# mirror_watchwinder.net
KiCad netlist of a schematic drawn in EAGLE
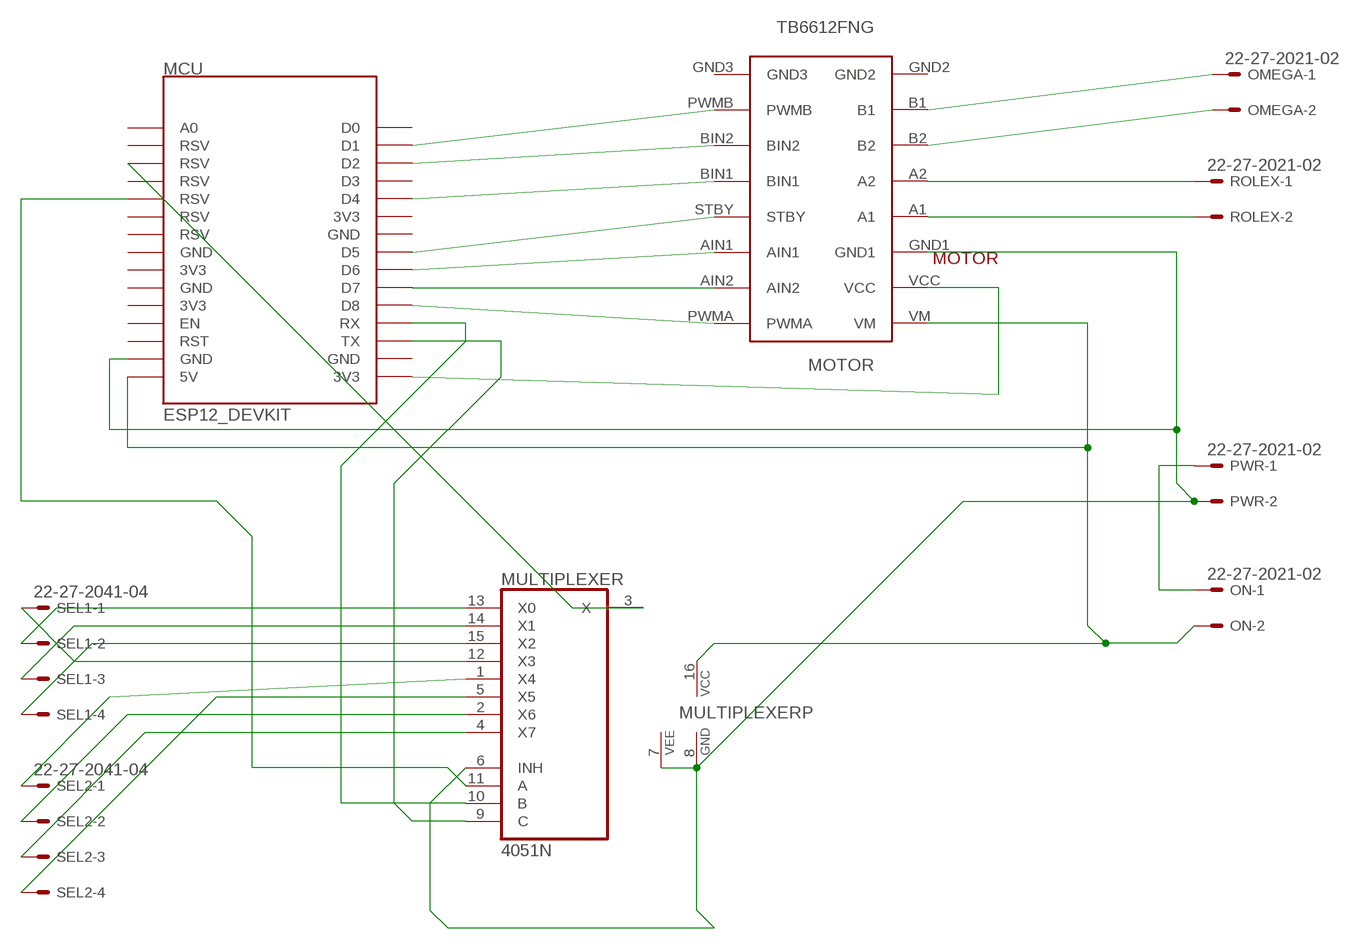
[diagram p0: schematic, sheet 1]

(export (version "E")
  (design (tool "Eeschema 10.0.6"))
  (components
    (comp (ref "MCU")
      (value "ESP12_DEVKIT")
      (footprint "eagle-import:ESP12_DEVKIT")
      (libsource (lib "eagle-import") (part "ESP12_DEVKIT"))
    )
    (comp (ref "MOTOR")
      (value "TB6612FNG")
      (footprint "eagle-import:TB6612FNG")
      (libsource (lib "eagle-import") (part "TB6612FNG"))
    )
    (comp (ref "MULTIPLEXER")
      (value "4051N")
      (footprint "eagle-import:DIL16")
      (libsource (lib "eagle-import") (part "4051N"))
    )
    (comp (ref "OMEGA")
      (value "22-27-2021-02")
      (footprint "eagle-import:6410-02")
      (libsource (lib "eagle-import") (part "22-?-0227-2021"))
    )
    (comp (ref "ON")
      (value "22-27-2021-02")
      (footprint "eagle-import:6410-02")
      (libsource (lib "eagle-import") (part "22-?-0227-2021"))
    )
    (comp (ref "PWR")
      (value "22-27-2021-02")
      (footprint "eagle-import:6410-02")
      (libsource (lib "eagle-import") (part "22-?-0227-2021"))
    )
    (comp (ref "ROLEX")
      (value "22-27-2021-02")
      (footprint "eagle-import:6410-02")
      (libsource (lib "eagle-import") (part "22-?-0227-2021"))
    )
    (comp (ref "SEL1")
      (value "22-27-2041-04")
      (footprint "eagle-import:6410-04")
      (libsource (lib "eagle-import") (part "22-?-0427-2041"))
    )
    (comp (ref "SEL2")
      (value "22-27-2041-04")
      (footprint "eagle-import:6410-04")
      (libsource (lib "eagle-import") (part "22-?-0427-2041"))
    )
  )
  (nets
    (net (code "1") (name "Net-(MCU-3V3-Pad3V3@2)") (class "Default")
      (node (ref "MCU") (pin "3V3@2") (pinfunction "3V3_3V3@2") (pintype "bidirectional"))
      (node (ref "MOTOR") (pin "VCC") (pinfunction "VCC_VCC") (pintype "bidirectional"))
    )
    (net (code "2") (name "Net-(MCU-PadD1)") (class "Default")
      (node (ref "MCU") (pin "D1") (pinfunction "D1_D1") (pintype "bidirectional"))
      (node (ref "MOTOR") (pin "PWMB") (pinfunction "PWMB_PWMB") (pintype "bidirectional"))
    )
    (net (code "3") (name "Net-(MCU-PadD2)") (class "Default")
      (node (ref "MCU") (pin "D2") (pinfunction "D2_D2") (pintype "bidirectional"))
      (node (ref "MOTOR") (pin "BIN2") (pinfunction "BIN2_BIN2") (pintype "bidirectional"))
    )
    (net (code "4") (name "Net-(MCU-PadD4)") (class "Default")
      (node (ref "MCU") (pin "D4") (pinfunction "D4_D4") (pintype "bidirectional"))
      (node (ref "MOTOR") (pin "BIN1") (pinfunction "BIN1_BIN1") (pintype "bidirectional"))
    )
    (net (code "5") (name "Net-(MCU-PadD5)") (class "Default")
      (node (ref "MCU") (pin "D5") (pinfunction "D5_D5") (pintype "bidirectional"))
      (node (ref "MOTOR") (pin "STBY") (pinfunction "STBY_STBY") (pintype "bidirectional"))
    )
    (net (code "6") (name "Net-(MCU-PadD6)") (class "Default")
      (node (ref "MCU") (pin "D6") (pinfunction "D6_D6") (pintype "bidirectional"))
      (node (ref "MOTOR") (pin "AIN1") (pinfunction "AIN1_AIN1") (pintype "bidirectional"))
    )
    (net (code "7") (name "Net-(MCU-PadD7)") (class "Default")
      (node (ref "MCU") (pin "D7") (pinfunction "D7_D7") (pintype "bidirectional"))
      (node (ref "MOTOR") (pin "AIN2") (pinfunction "AIN2_AIN2") (pintype "bidirectional"))
    )
    (net (code "8") (name "Net-(MCU-PadD8)") (class "Default")
      (node (ref "MCU") (pin "D8") (pinfunction "D8_D8") (pintype "bidirectional"))
      (node (ref "MOTOR") (pin "PWMA") (pinfunction "PWMA_PWMA") (pintype "bidirectional"))
    )
    (net (code "9") (name "Net-(MULTIPLEXERA-A)") (class "Default")
      (node (ref "MCU") (pin "RSV@3") (pinfunction "RSV_RSV@3") (pintype "bidirectional"))
      (node (ref "MULTIPLEXER") (pin "11") (pinfunction "A_11") (pintype "input"))
    )
    (net (code "10") (name "Net-(MULTIPLEXERA-B)") (class "Default")
      (node (ref "MCU") (pin "RX") (pinfunction "RX_RX") (pintype "bidirectional"))
      (node (ref "MULTIPLEXER") (pin "10") (pinfunction "B_10") (pintype "input"))
    )
    (net (code "11") (name "Net-(MULTIPLEXERA-C)") (class "Default")
      (node (ref "MCU") (pin "TX") (pinfunction "TX_TX") (pintype "bidirectional"))
      (node (ref "MULTIPLEXER") (pin "9") (pinfunction "C_9") (pintype "input"))
    )
    (net (code "12") (name "Net-(MULTIPLEXERA-INH)") (class "Default")
      (node (ref "MCU") (pin "GND@1") (pinfunction "GND_GND@1") (pintype "bidirectional"))
      (node (ref "MOTOR") (pin "GND1") (pinfunction "GND1_GND1") (pintype "bidirectional"))
      (node (ref "MULTIPLEXER") (pin "6") (pinfunction "INH_6") (pintype "input"))
      (node (ref "MULTIPLEXER") (pin "7") (pinfunction "VEE_7") (pintype "power_in"))
      (node (ref "MULTIPLEXER") (pin "8") (pinfunction "GND_8") (pintype "power_in"))
      (node (ref "PWR") (pin "2") (pinfunction "S_2") (pintype "passive"))
    )
    (net (code "13") (name "Net-(MULTIPLEXERA-X)") (class "Default")
      (node (ref "MCU") (pin "RSV@1") (pinfunction "RSV_RSV@1") (pintype "bidirectional"))
      (node (ref "MULTIPLEXER") (pin "3") (pinfunction "X_3") (pintype "bidirectional"))
    )
    (net (code "14") (name "Net-(MULTIPLEXERA-X0)") (class "Default")
      (node (ref "MULTIPLEXER") (pin "13") (pinfunction "X0_13") (pintype "bidirectional"))
      (node (ref "SEL1") (pin "2") (pinfunction "S_2") (pintype "passive"))
    )
    (net (code "15") (name "Net-(MULTIPLEXERA-X1)") (class "Default")
      (node (ref "MULTIPLEXER") (pin "14") (pinfunction "X1_14") (pintype "bidirectional"))
      (node (ref "SEL1") (pin "3") (pinfunction "S_3") (pintype "passive"))
    )
    (net (code "16") (name "Net-(MULTIPLEXERA-X2)") (class "Default")
      (node (ref "MULTIPLEXER") (pin "15") (pinfunction "X2_15") (pintype "bidirectional"))
      (node (ref "SEL1") (pin "4") (pinfunction "S_4") (pintype "passive"))
    )
    (net (code "17") (name "Net-(MULTIPLEXERA-X3)") (class "Default")
      (node (ref "MULTIPLEXER") (pin "12") (pinfunction "X3_12") (pintype "bidirectional"))
      (node (ref "SEL1") (pin "1") (pinfunction "S_1") (pintype "passive"))
    )
    (net (code "18") (name "Net-(MULTIPLEXERA-X4)") (class "Default")
      (node (ref "MULTIPLEXER") (pin "1") (pinfunction "X4_1") (pintype "bidirectional"))
      (node (ref "SEL2") (pin "1") (pinfunction "S_1") (pintype "passive"))
    )
    (net (code "19") (name "Net-(MULTIPLEXERA-X5)") (class "Default")
      (node (ref "MULTIPLEXER") (pin "5") (pinfunction "X5_5") (pintype "bidirectional"))
      (node (ref "SEL2") (pin "4") (pinfunction "S_4") (pintype "passive"))
    )
    (net (code "20") (name "Net-(MULTIPLEXERA-X6)") (class "Default")
      (node (ref "MULTIPLEXER") (pin "2") (pinfunction "X6_2") (pintype "bidirectional"))
      (node (ref "SEL2") (pin "2") (pinfunction "S_2") (pintype "passive"))
    )
    (net (code "21") (name "Net-(MULTIPLEXERA-X7)") (class "Default")
      (node (ref "MULTIPLEXER") (pin "4") (pinfunction "X7_4") (pintype "bidirectional"))
      (node (ref "SEL2") (pin "3") (pinfunction "S_3") (pintype "passive"))
    )
    (net (code "22") (name "Net-(MULTIPLEXERB-VCC)") (class "Default")
      (node (ref "MCU") (pin "5V") (pinfunction "5V_5V") (pintype "bidirectional"))
      (node (ref "MOTOR") (pin "VM") (pinfunction "VM_VM") (pintype "bidirectional"))
      (node (ref "MULTIPLEXER") (pin "16") (pinfunction "VCC_16") (pintype "power_in"))
      (node (ref "ON") (pin "2") (pinfunction "S_2") (pintype "passive"))
    )
    (net (code "23") (name "Net-(OMEGAA-S)") (class "Default")
      (node (ref "MOTOR") (pin "B1") (pinfunction "B1_B1") (pintype "bidirectional"))
      (node (ref "OMEGA") (pin "1") (pinfunction "S_1") (pintype "passive"))
    )
    (net (code "24") (name "Net-(OMEGAB-S)") (class "Default")
      (node (ref "MOTOR") (pin "B2") (pinfunction "B2_B2") (pintype "bidirectional"))
      (node (ref "OMEGA") (pin "2") (pinfunction "S_2") (pintype "passive"))
    )
    (net (code "25") (name "Net-(ONA-S)") (class "Default")
      (node (ref "ON") (pin "1") (pinfunction "S_1") (pintype "passive"))
      (node (ref "PWR") (pin "1") (pinfunction "S_1") (pintype "passive"))
    )
    (net (code "26") (name "Net-(ROLEXA-S)") (class "Default")
      (node (ref "MOTOR") (pin "A2") (pinfunction "A2_A2") (pintype "bidirectional"))
      (node (ref "ROLEX") (pin "1") (pinfunction "S_1") (pintype "passive"))
    )
    (net (code "27") (name "Net-(ROLEXB-S)") (class "Default")
      (node (ref "MOTOR") (pin "A1") (pinfunction "A1_A1") (pintype "bidirectional"))
      (node (ref "ROLEX") (pin "2") (pinfunction "S_2") (pintype "passive"))
    )
    (net (code "28") (name "unconnected-(MCU-3V3-Pad3V3@0)") (class "Default")
      (node (ref "MCU") (pin "3V3@0") (pinfunction "3V3_3V3@0") (pintype "bidirectional"))
    )
    (net (code "29") (name "unconnected-(MCU-3V3-Pad3V3@1)") (class "Default")
      (node (ref "MCU") (pin "3V3@1") (pinfunction "3V3_3V3@1") (pintype "bidirectional"))
    )
    (net (code "30") (name "unconnected-(MCU-3V3-Pad3V3@3)") (class "Default")
      (node (ref "MCU") (pin "3V3@3") (pinfunction "3V3_3V3@3") (pintype "bidirectional"))
    )
    (net (code "31") (name "unconnected-(MCU-GND-PadGND@0)") (class "Default")
      (node (ref "MCU") (pin "GND@0") (pinfunction "GND_GND@0") (pintype "bidirectional"))
    )
    (net (code "32") (name "unconnected-(MCU-GND-PadGND@2)") (class "Default")
      (node (ref "MCU") (pin "GND@2") (pinfunction "GND_GND@2") (pintype "bidirectional"))
    )
    (net (code "33") (name "unconnected-(MCU-GND-PadGND@3)") (class "Default")
      (node (ref "MCU") (pin "GND@3") (pinfunction "GND_GND@3") (pintype "bidirectional"))
    )
    (net (code "34") (name "unconnected-(MCU-GND-PadGND@4)") (class "Default")
      (node (ref "MCU") (pin "GND@4") (pinfunction "GND_GND@4") (pintype "bidirectional"))
    )
    (net (code "35") (name "unconnected-(MCU-PadA0)") (class "Default")
      (node (ref "MCU") (pin "A0") (pinfunction "A0_A0") (pintype "bidirectional"))
    )
    (net (code "36") (name "unconnected-(MCU-PadD0)") (class "Default")
      (node (ref "MCU") (pin "D0") (pinfunction "D0_D0") (pintype "bidirectional"))
    )
    (net (code "37") (name "unconnected-(MCU-PadD3)") (class "Default")
      (node (ref "MCU") (pin "D3") (pinfunction "D3_D3") (pintype "bidirectional"))
    )
    (net (code "38") (name "unconnected-(MCU-PadEN)") (class "Default")
      (node (ref "MCU") (pin "EN") (pinfunction "EN_EN") (pintype "bidirectional"))
    )
    (net (code "39") (name "unconnected-(MCU-PadRST)") (class "Default")
      (node (ref "MCU") (pin "RST") (pinfunction "RST_RST") (pintype "bidirectional"))
    )
    (net (code "40") (name "unconnected-(MCU-RSV-PadRSV@0)") (class "Default")
      (node (ref "MCU") (pin "RSV@0") (pinfunction "RSV_RSV@0") (pintype "bidirectional"))
    )
    (net (code "41") (name "unconnected-(MCU-RSV-PadRSV@2)") (class "Default")
      (node (ref "MCU") (pin "RSV@2") (pinfunction "RSV_RSV@2") (pintype "bidirectional"))
    )
    (net (code "42") (name "unconnected-(MCU-RSV-PadRSV@4)") (class "Default")
      (node (ref "MCU") (pin "RSV@4") (pinfunction "RSV_RSV@4") (pintype "bidirectional"))
    )
    (net (code "43") (name "unconnected-(MCU-RSV-PadRSV@5)") (class "Default")
      (node (ref "MCU") (pin "RSV@5") (pinfunction "RSV_RSV@5") (pintype "bidirectional"))
    )
    (net (code "44") (name "unconnected-(MOTOR-PadGND2)") (class "Default")
      (node (ref "MOTOR") (pin "GND2") (pinfunction "GND2_GND2") (pintype "bidirectional"))
    )
    (net (code "45") (name "unconnected-(MOTOR-PadGND3)") (class "Default")
      (node (ref "MOTOR") (pin "GND3") (pinfunction "GND3_GND3") (pintype "bidirectional"))
    )
  )
)
